# R601F.net
KiCad netlist of a schematic drawn in EAGLE
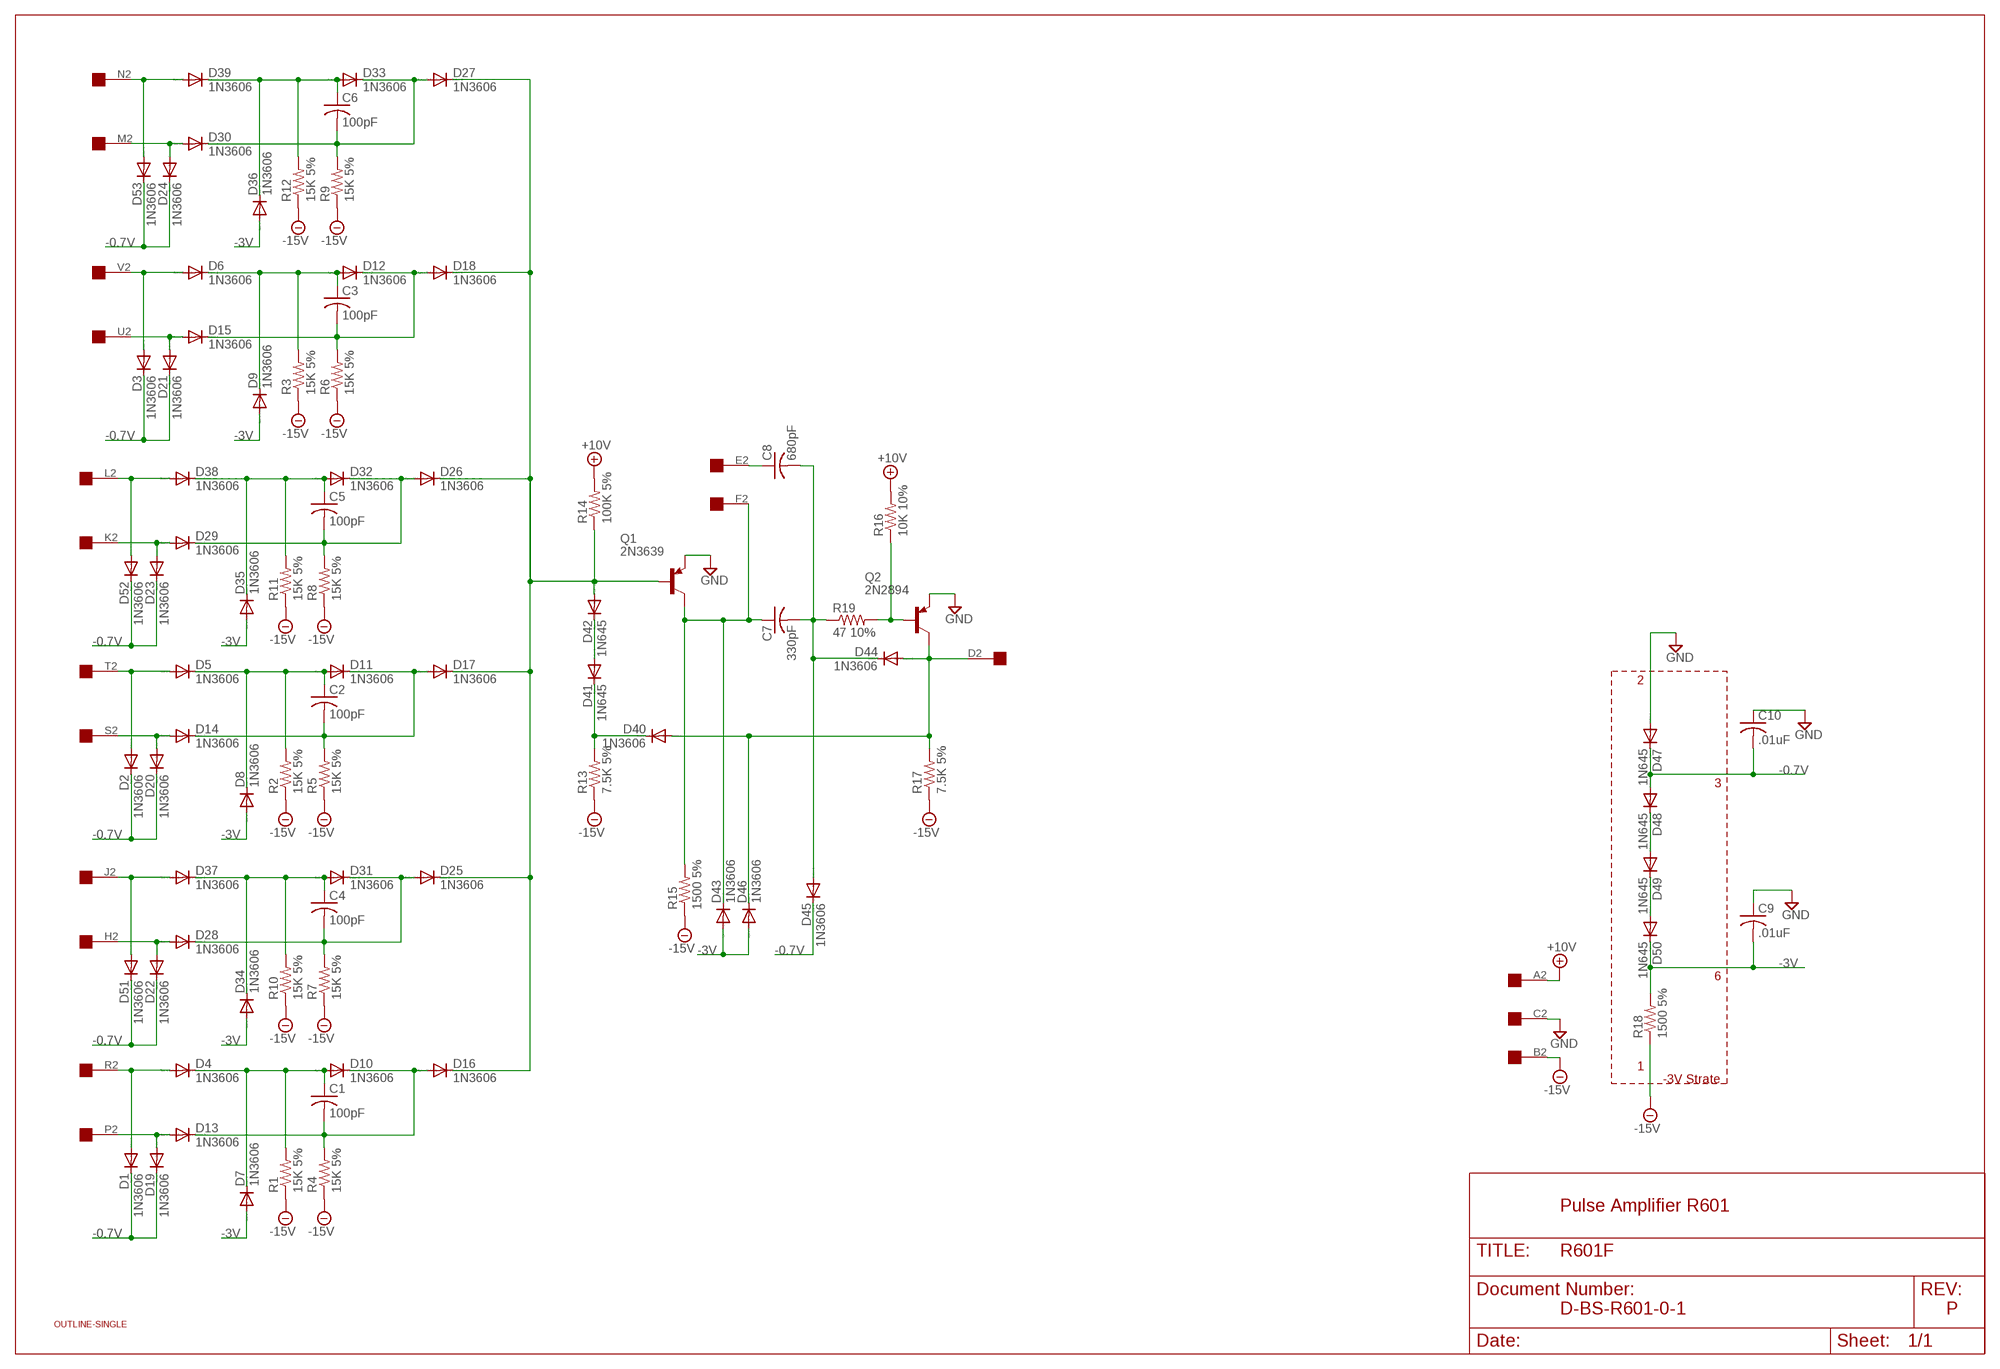
[diagram p0: schematic, sheet 1]

(export (version "E")
  (design (tool "Eeschema 10.0.6"))
  (components
    (comp (ref "C1")
      (value "100pF")
      (footprint "eagle-import:C050-025X075")
      (libsource (lib "eagle-import") (part "C-US050-025X075"))
    )
    (comp (ref "C2")
      (value "100pF")
      (footprint "eagle-import:C050-025X075")
      (libsource (lib "eagle-import") (part "C-US050-025X075"))
    )
    (comp (ref "C3")
      (value "100pF")
      (footprint "eagle-import:C050-025X075")
      (libsource (lib "eagle-import") (part "C-US050-025X075"))
    )
    (comp (ref "C4")
      (value "100pF")
      (footprint "eagle-import:C050-025X075")
      (libsource (lib "eagle-import") (part "C-US050-025X075"))
    )
    (comp (ref "C5")
      (value "100pF")
      (footprint "eagle-import:C050-025X075")
      (libsource (lib "eagle-import") (part "C-US050-025X075"))
    )
    (comp (ref "C6")
      (value "100pF")
      (footprint "eagle-import:C050-025X075")
      (libsource (lib "eagle-import") (part "C-US050-025X075"))
    )
    (comp (ref "C7")
      (value "330pF")
      (footprint "eagle-import:C050-025X075")
      (libsource (lib "eagle-import") (part "C-US050-025X075"))
    )
    (comp (ref "C8")
      (value "680pF")
      (footprint "eagle-import:C050-025X075")
      (libsource (lib "eagle-import") (part "C-US050-025X075"))
    )
    (comp (ref "C9")
      (value ".01uF")
      (footprint "eagle-import:C050-025X075")
      (libsource (lib "eagle-import") (part "C-US050-025X075"))
    )
    (comp (ref "C10")
      (value ".01uF")
      (footprint "eagle-import:C050-025X075")
      (libsource (lib "eagle-import") (part "C-US050-025X075"))
    )
    (comp (ref "D1")
      (value "1N3606")
      (footprint "eagle-import:DO35-10")
      (libsource (lib "eagle-import") (part "1N4148DO35-10"))
    )
    (comp (ref "D2")
      (value "1N3606")
      (footprint "eagle-import:DO35-10")
      (libsource (lib "eagle-import") (part "1N4148DO35-10"))
    )
    (comp (ref "D3")
      (value "1N3606")
      (footprint "eagle-import:DO35-10")
      (libsource (lib "eagle-import") (part "1N4148DO35-10"))
    )
    (comp (ref "D4")
      (value "1N3606")
      (footprint "eagle-import:DO35-10")
      (libsource (lib "eagle-import") (part "1N4148DO35-10"))
    )
    (comp (ref "D5")
      (value "1N3606")
      (footprint "eagle-import:DO35-10")
      (libsource (lib "eagle-import") (part "1N4148DO35-10"))
    )
    (comp (ref "D6")
      (value "1N3606")
      (footprint "eagle-import:DO35-10")
      (libsource (lib "eagle-import") (part "1N4148DO35-10"))
    )
    (comp (ref "D7")
      (value "1N3606")
      (footprint "eagle-import:DO35-10")
      (libsource (lib "eagle-import") (part "1N4148DO35-10"))
    )
    (comp (ref "D8")
      (value "1N3606")
      (footprint "eagle-import:DO35-10")
      (libsource (lib "eagle-import") (part "1N4148DO35-10"))
    )
    (comp (ref "D9")
      (value "1N3606")
      (footprint "eagle-import:DO35-10")
      (libsource (lib "eagle-import") (part "1N4148DO35-10"))
    )
    (comp (ref "D10")
      (value "1N3606")
      (footprint "eagle-import:DO35-10")
      (libsource (lib "eagle-import") (part "1N4148DO35-10"))
    )
    (comp (ref "D11")
      (value "1N3606")
      (footprint "eagle-import:DO35-10")
      (libsource (lib "eagle-import") (part "1N4148DO35-10"))
    )
    (comp (ref "D12")
      (value "1N3606")
      (footprint "eagle-import:DO35-10")
      (libsource (lib "eagle-import") (part "1N4148DO35-10"))
    )
    (comp (ref "D13")
      (value "1N3606")
      (footprint "eagle-import:DO35-10")
      (libsource (lib "eagle-import") (part "1N4148DO35-10"))
    )
    (comp (ref "D14")
      (value "1N3606")
      (footprint "eagle-import:DO35-10")
      (libsource (lib "eagle-import") (part "1N4148DO35-10"))
    )
    (comp (ref "D15")
      (value "1N3606")
      (footprint "eagle-import:DO35-10")
      (libsource (lib "eagle-import") (part "1N4148DO35-10"))
    )
    (comp (ref "D16")
      (value "1N3606")
      (footprint "eagle-import:DO35-10")
      (libsource (lib "eagle-import") (part "1N4148DO35-10"))
    )
    (comp (ref "D17")
      (value "1N3606")
      (footprint "eagle-import:DO35-10")
      (libsource (lib "eagle-import") (part "1N4148DO35-10"))
    )
    (comp (ref "D18")
      (value "1N3606")
      (footprint "eagle-import:DO35-10")
      (libsource (lib "eagle-import") (part "1N4148DO35-10"))
    )
    (comp (ref "D19")
      (value "1N3606")
      (footprint "eagle-import:DO35-10")
      (libsource (lib "eagle-import") (part "1N4148DO35-10"))
    )
    (comp (ref "D20")
      (value "1N3606")
      (footprint "eagle-import:DO35-10")
      (libsource (lib "eagle-import") (part "1N4148DO35-10"))
    )
    (comp (ref "D21")
      (value "1N3606")
      (footprint "eagle-import:DO35-10")
      (libsource (lib "eagle-import") (part "1N4148DO35-10"))
    )
    (comp (ref "D22")
      (value "1N3606")
      (footprint "eagle-import:DO35-10")
      (libsource (lib "eagle-import") (part "1N4148DO35-10"))
    )
    (comp (ref "D23")
      (value "1N3606")
      (footprint "eagle-import:DO35-10")
      (libsource (lib "eagle-import") (part "1N4148DO35-10"))
    )
    (comp (ref "D24")
      (value "1N3606")
      (footprint "eagle-import:DO35-10")
      (libsource (lib "eagle-import") (part "1N4148DO35-10"))
    )
    (comp (ref "D25")
      (value "1N3606")
      (footprint "eagle-import:DO35-10")
      (libsource (lib "eagle-import") (part "1N4148DO35-10"))
    )
    (comp (ref "D26")
      (value "1N3606")
      (footprint "eagle-import:DO35-10")
      (libsource (lib "eagle-import") (part "1N4148DO35-10"))
    )
    (comp (ref "D27")
      (value "1N3606")
      (footprint "eagle-import:DO35-10")
      (libsource (lib "eagle-import") (part "1N4148DO35-10"))
    )
    (comp (ref "D28")
      (value "1N3606")
      (footprint "eagle-import:DO35-10")
      (libsource (lib "eagle-import") (part "1N4148DO35-10"))
    )
    (comp (ref "D29")
      (value "1N3606")
      (footprint "eagle-import:DO35-10")
      (libsource (lib "eagle-import") (part "1N4148DO35-10"))
    )
    (comp (ref "D30")
      (value "1N3606")
      (footprint "eagle-import:DO35-10")
      (libsource (lib "eagle-import") (part "1N4148DO35-10"))
    )
    (comp (ref "D31")
      (value "1N3606")
      (footprint "eagle-import:DO35-10")
      (libsource (lib "eagle-import") (part "1N4148DO35-10"))
    )
    (comp (ref "D32")
      (value "1N3606")
      (footprint "eagle-import:DO35-10")
      (libsource (lib "eagle-import") (part "1N4148DO35-10"))
    )
    (comp (ref "D33")
      (value "1N3606")
      (footprint "eagle-import:DO35-10")
      (libsource (lib "eagle-import") (part "1N4148DO35-10"))
    )
    (comp (ref "D34")
      (value "1N3606")
      (footprint "eagle-import:DO35-10")
      (libsource (lib "eagle-import") (part "1N4148DO35-10"))
    )
    (comp (ref "D35")
      (value "1N3606")
      (footprint "eagle-import:DO35-10")
      (libsource (lib "eagle-import") (part "1N4148DO35-10"))
    )
    (comp (ref "D36")
      (value "1N3606")
      (footprint "eagle-import:DO35-10")
      (libsource (lib "eagle-import") (part "1N4148DO35-10"))
    )
    (comp (ref "D37")
      (value "1N3606")
      (footprint "eagle-import:DO35-10")
      (libsource (lib "eagle-import") (part "1N4148DO35-10"))
    )
    (comp (ref "D38")
      (value "1N3606")
      (footprint "eagle-import:DO35-10")
      (libsource (lib "eagle-import") (part "1N4148DO35-10"))
    )
    (comp (ref "D39")
      (value "1N3606")
      (footprint "eagle-import:DO35-10")
      (libsource (lib "eagle-import") (part "1N4148DO35-10"))
    )
    (comp (ref "D40")
      (value "1N3606")
      (footprint "eagle-import:DO35-10")
      (libsource (lib "eagle-import") (part "1N4148DO35-10"))
    )
    (comp (ref "D41")
      (value "1N645")
      (footprint "eagle-import:DO35-10")
      (libsource (lib "eagle-import") (part "1N4148DO35-10"))
    )
    (comp (ref "D42")
      (value "1N645")
      (footprint "eagle-import:DO35-10")
      (libsource (lib "eagle-import") (part "1N4148DO35-10"))
    )
    (comp (ref "D43")
      (value "1N3606")
      (footprint "eagle-import:DO35-10")
      (libsource (lib "eagle-import") (part "1N4148DO35-10"))
    )
    (comp (ref "D44")
      (value "1N3606")
      (footprint "eagle-import:DO35-10")
      (libsource (lib "eagle-import") (part "1N4148DO35-10"))
    )
    (comp (ref "D45")
      (value "1N3606")
      (footprint "eagle-import:DO35-10")
      (libsource (lib "eagle-import") (part "1N4148DO35-10"))
    )
    (comp (ref "D46")
      (value "1N3606")
      (footprint "eagle-import:DO35-10")
      (libsource (lib "eagle-import") (part "1N4148DO35-10"))
    )
    (comp (ref "D47")
      (value "1N645")
      (footprint "eagle-import:DO35-10")
      (libsource (lib "eagle-import") (part "1N4148DO35-10"))
    )
    (comp (ref "D48")
      (value "1N645")
      (footprint "eagle-import:DO35-10")
      (libsource (lib "eagle-import") (part "1N4148DO35-10"))
    )
    (comp (ref "D49")
      (value "1N645")
      (footprint "eagle-import:DO35-10")
      (libsource (lib "eagle-import") (part "1N4148DO35-10"))
    )
    (comp (ref "D50")
      (value "1N645")
      (footprint "eagle-import:DO35-10")
      (libsource (lib "eagle-import") (part "1N4148DO35-10"))
    )
    (comp (ref "D51")
      (value "1N3606")
      (footprint "eagle-import:DO35-10")
      (libsource (lib "eagle-import") (part "1N4148DO35-10"))
    )
    (comp (ref "D52")
      (value "1N3606")
      (footprint "eagle-import:DO35-10")
      (libsource (lib "eagle-import") (part "1N4148DO35-10"))
    )
    (comp (ref "D53")
      (value "1N3606")
      (footprint "eagle-import:DO35-10")
      (libsource (lib "eagle-import") (part "1N4148DO35-10"))
    )
    (comp (ref "Q1")
      (value "2N3639")
      (footprint "eagle-import:TO39")
      (libsource (lib "eagle-import") (part "2N2904"))
    )
    (comp (ref "Q2")
      (value "2N2894")
      (footprint "eagle-import:TO39")
      (libsource (lib "eagle-import") (part "2N2904"))
    )
    (comp (ref "R1")
      (value "15K 5%")
      (footprint "eagle-import:0207_10")
      (libsource (lib "eagle-import") (part "R-US_0207/10"))
    )
    (comp (ref "R2")
      (value "15K 5%")
      (footprint "eagle-import:0207_10")
      (libsource (lib "eagle-import") (part "R-US_0207/10"))
    )
    (comp (ref "R3")
      (value "15K 5%")
      (footprint "eagle-import:0207_10")
      (libsource (lib "eagle-import") (part "R-US_0207/10"))
    )
    (comp (ref "R4")
      (value "15K 5%")
      (footprint "eagle-import:0207_10")
      (libsource (lib "eagle-import") (part "R-US_0207/10"))
    )
    (comp (ref "R5")
      (value "15K 5%")
      (footprint "eagle-import:0207_10")
      (libsource (lib "eagle-import") (part "R-US_0207/10"))
    )
    (comp (ref "R6")
      (value "15K 5%")
      (footprint "eagle-import:0207_10")
      (libsource (lib "eagle-import") (part "R-US_0207/10"))
    )
    (comp (ref "R7")
      (value "15K 5%")
      (footprint "eagle-import:0207_10")
      (libsource (lib "eagle-import") (part "R-US_0207/10"))
    )
    (comp (ref "R8")
      (value "15K 5%")
      (footprint "eagle-import:0207_10")
      (libsource (lib "eagle-import") (part "R-US_0207/10"))
    )
    (comp (ref "R9")
      (value "15K 5%")
      (footprint "eagle-import:0207_10")
      (libsource (lib "eagle-import") (part "R-US_0207/10"))
    )
    (comp (ref "R10")
      (value "15K 5%")
      (footprint "eagle-import:0207_10")
      (libsource (lib "eagle-import") (part "R-US_0207/10"))
    )
    (comp (ref "R11")
      (value "15K 5%")
      (footprint "eagle-import:0207_10")
      (libsource (lib "eagle-import") (part "R-US_0207/10"))
    )
    (comp (ref "R12")
      (value "15K 5%")
      (footprint "eagle-import:0207_10")
      (libsource (lib "eagle-import") (part "R-US_0207/10"))
    )
    (comp (ref "R13")
      (value "7.5K 5%")
      (footprint "eagle-import:0207_10")
      (libsource (lib "eagle-import") (part "R-US_0207/10"))
    )
    (comp (ref "R14")
      (value "100K 5%")
      (footprint "eagle-import:0207_10")
      (libsource (lib "eagle-import") (part "R-US_0207/10"))
    )
    (comp (ref "R15")
      (value "1500 5%")
      (footprint "eagle-import:0207_10")
      (libsource (lib "eagle-import") (part "R-US_0207/10"))
    )
    (comp (ref "R16")
      (value "10K 10%")
      (footprint "eagle-import:0207_10")
      (libsource (lib "eagle-import") (part "R-US_0207/10"))
    )
    (comp (ref "R17")
      (value "7.5K 5%")
      (footprint "eagle-import:0207_10")
      (libsource (lib "eagle-import") (part "R-US_0207/10"))
    )
    (comp (ref "R18")
      (value "1500 5%")
      (footprint "eagle-import:0207_10")
      (libsource (lib "eagle-import") (part "R-US_0207/10"))
    )
    (comp (ref "R19")
      (value "47 10%")
      (footprint "eagle-import:0207_10")
      (libsource (lib "eagle-import") (part "R-US_0207/10"))
    )
    (comp (ref "U$1")
      (value "OUTLINE-SINGLE")
      (footprint "eagle-import:SINGLE")
      (libsource (lib "eagle-import") (part "OUTLINE-SINGLE"))
    )
    (comp (ref "U$2")
      (value "EDGE-1")
      (footprint "eagle-import:EDGE-CON1")
      (libsource (lib "eagle-import") (part "EDGE-1"))
    )
  )
  (nets
    (net (code "1") (name "+10V") (class "Default")
      (node (ref "R14") (pin "2") (pinfunction "2_2") (pintype "passive"))
      (node (ref "R16") (pin "2") (pinfunction "2_2") (pintype "passive"))
      (node (ref "U$2") (pin "A2") (pinfunction "1_A2") (pintype "bidirectional"))
    )
    (net (code "2") (name "-15V") (class "Default")
      (node (ref "R1") (pin "1") (pinfunction "1_1") (pintype "passive"))
      (node (ref "R10") (pin "1") (pinfunction "1_1") (pintype "passive"))
      (node (ref "R11") (pin "1") (pinfunction "1_1") (pintype "passive"))
      (node (ref "R12") (pin "1") (pinfunction "1_1") (pintype "passive"))
      (node (ref "R13") (pin "1") (pinfunction "1_1") (pintype "passive"))
      (node (ref "R15") (pin "1") (pinfunction "1_1") (pintype "passive"))
      (node (ref "R17") (pin "1") (pinfunction "1_1") (pintype "passive"))
      (node (ref "R18") (pin "1") (pinfunction "1_1") (pintype "passive"))
      (node (ref "R2") (pin "1") (pinfunction "1_1") (pintype "passive"))
      (node (ref "R3") (pin "1") (pinfunction "1_1") (pintype "passive"))
      (node (ref "R4") (pin "1") (pinfunction "1_1") (pintype "passive"))
      (node (ref "R5") (pin "1") (pinfunction "1_1") (pintype "passive"))
      (node (ref "R6") (pin "1") (pinfunction "1_1") (pintype "passive"))
      (node (ref "R7") (pin "1") (pinfunction "1_1") (pintype "passive"))
      (node (ref "R8") (pin "1") (pinfunction "1_1") (pintype "passive"))
      (node (ref "R9") (pin "1") (pinfunction "1_1") (pintype "passive"))
      (node (ref "U$2") (pin "B2") (pinfunction "1_B2") (pintype "bidirectional"))
    )
    (net (code "3") (name "/-0.7V") (class "Default")
      (node (ref "C10") (pin "2") (pinfunction "2_2") (pintype "passive"))
      (node (ref "D1") (pin "C") (pinfunction "C_C") (pintype "passive"))
      (node (ref "D19") (pin "C") (pinfunction "C_C") (pintype "passive"))
      (node (ref "D2") (pin "C") (pinfunction "C_C") (pintype "passive"))
      (node (ref "D20") (pin "C") (pinfunction "C_C") (pintype "passive"))
      (node (ref "D21") (pin "C") (pinfunction "C_C") (pintype "passive"))
      (node (ref "D22") (pin "C") (pinfunction "C_C") (pintype "passive"))
      (node (ref "D23") (pin "C") (pinfunction "C_C") (pintype "passive"))
      (node (ref "D24") (pin "C") (pinfunction "C_C") (pintype "passive"))
      (node (ref "D3") (pin "C") (pinfunction "C_C") (pintype "passive"))
      (node (ref "D45") (pin "C") (pinfunction "C_C") (pintype "passive"))
      (node (ref "D47") (pin "C") (pinfunction "C_C") (pintype "passive"))
      (node (ref "D48") (pin "A") (pinfunction "A_A") (pintype "passive"))
      (node (ref "D51") (pin "C") (pinfunction "C_C") (pintype "passive"))
      (node (ref "D52") (pin "C") (pinfunction "C_C") (pintype "passive"))
      (node (ref "D53") (pin "C") (pinfunction "C_C") (pintype "passive"))
    )
    (net (code "4") (name "/-3V") (class "Default")
      (node (ref "C9") (pin "2") (pinfunction "2_2") (pintype "passive"))
      (node (ref "D34") (pin "A") (pinfunction "A_A") (pintype "passive"))
      (node (ref "D35") (pin "A") (pinfunction "A_A") (pintype "passive"))
      (node (ref "D36") (pin "A") (pinfunction "A_A") (pintype "passive"))
      (node (ref "D43") (pin "A") (pinfunction "A_A") (pintype "passive"))
      (node (ref "D46") (pin "A") (pinfunction "A_A") (pintype "passive"))
      (node (ref "D50") (pin "C") (pinfunction "C_C") (pintype "passive"))
      (node (ref "D7") (pin "A") (pinfunction "A_A") (pintype "passive"))
      (node (ref "D8") (pin "A") (pinfunction "A_A") (pintype "passive"))
      (node (ref "D9") (pin "A") (pinfunction "A_A") (pintype "passive"))
      (node (ref "R18") (pin "2") (pinfunction "2_2") (pintype "passive"))
    )
    (net (code "5") (name "GND") (class "Default")
      (node (ref "C10") (pin "1") (pinfunction "1_1") (pintype "passive"))
      (node (ref "C9") (pin "1") (pinfunction "1_1") (pintype "passive"))
      (node (ref "D47") (pin "A") (pinfunction "A_A") (pintype "passive"))
      (node (ref "Q1") (pin "1") (pinfunction "E_1") (pintype "passive"))
      (node (ref "Q2") (pin "1") (pinfunction "E_1") (pintype "passive"))
      (node (ref "U$2") (pin "C2") (pinfunction "1_C2") (pintype "bidirectional"))
    )
    (net (code "6") (name "Net-(C1-Pad1)") (class "Default")
      (node (ref "C1") (pin "1") (pinfunction "1_1") (pintype "passive"))
      (node (ref "D10") (pin "A") (pinfunction "A_A") (pintype "passive"))
      (node (ref "D4") (pin "C") (pinfunction "C_C") (pintype "passive"))
      (node (ref "D7") (pin "C") (pinfunction "C_C") (pintype "passive"))
      (node (ref "R1") (pin "2") (pinfunction "2_2") (pintype "passive"))
    )
    (net (code "7") (name "Net-(C1-Pad2)") (class "Default")
      (node (ref "C1") (pin "2") (pinfunction "2_2") (pintype "passive"))
      (node (ref "D10") (pin "C") (pinfunction "C_C") (pintype "passive"))
      (node (ref "D13") (pin "C") (pinfunction "C_C") (pintype "passive"))
      (node (ref "D16") (pin "A") (pinfunction "A_A") (pintype "passive"))
      (node (ref "R4") (pin "2") (pinfunction "2_2") (pintype "passive"))
    )
    (net (code "8") (name "Net-(C2-Pad1)") (class "Default")
      (node (ref "C2") (pin "1") (pinfunction "1_1") (pintype "passive"))
      (node (ref "D11") (pin "A") (pinfunction "A_A") (pintype "passive"))
      (node (ref "D5") (pin "C") (pinfunction "C_C") (pintype "passive"))
      (node (ref "D8") (pin "C") (pinfunction "C_C") (pintype "passive"))
      (node (ref "R2") (pin "2") (pinfunction "2_2") (pintype "passive"))
    )
    (net (code "9") (name "Net-(C2-Pad2)") (class "Default")
      (node (ref "C2") (pin "2") (pinfunction "2_2") (pintype "passive"))
      (node (ref "D11") (pin "C") (pinfunction "C_C") (pintype "passive"))
      (node (ref "D14") (pin "C") (pinfunction "C_C") (pintype "passive"))
      (node (ref "D17") (pin "A") (pinfunction "A_A") (pintype "passive"))
      (node (ref "R5") (pin "2") (pinfunction "2_2") (pintype "passive"))
    )
    (net (code "10") (name "Net-(C3-Pad1)") (class "Default")
      (node (ref "C3") (pin "1") (pinfunction "1_1") (pintype "passive"))
      (node (ref "D12") (pin "A") (pinfunction "A_A") (pintype "passive"))
      (node (ref "D6") (pin "C") (pinfunction "C_C") (pintype "passive"))
      (node (ref "D9") (pin "C") (pinfunction "C_C") (pintype "passive"))
      (node (ref "R3") (pin "2") (pinfunction "2_2") (pintype "passive"))
    )
    (net (code "11") (name "Net-(C3-Pad2)") (class "Default")
      (node (ref "C3") (pin "2") (pinfunction "2_2") (pintype "passive"))
      (node (ref "D12") (pin "C") (pinfunction "C_C") (pintype "passive"))
      (node (ref "D15") (pin "C") (pinfunction "C_C") (pintype "passive"))
      (node (ref "D18") (pin "A") (pinfunction "A_A") (pintype "passive"))
      (node (ref "R6") (pin "2") (pinfunction "2_2") (pintype "passive"))
    )
    (net (code "12") (name "Net-(C4-Pad1)") (class "Default")
      (node (ref "C4") (pin "1") (pinfunction "1_1") (pintype "passive"))
      (node (ref "D31") (pin "A") (pinfunction "A_A") (pintype "passive"))
      (node (ref "D34") (pin "C") (pinfunction "C_C") (pintype "passive"))
      (node (ref "D37") (pin "C") (pinfunction "C_C") (pintype "passive"))
      (node (ref "R10") (pin "2") (pinfunction "2_2") (pintype "passive"))
    )
    (net (code "13") (name "Net-(C4-Pad2)") (class "Default")
      (node (ref "C4") (pin "2") (pinfunction "2_2") (pintype "passive"))
      (node (ref "D25") (pin "A") (pinfunction "A_A") (pintype "passive"))
      (node (ref "D28") (pin "C") (pinfunction "C_C") (pintype "passive"))
      (node (ref "D31") (pin "C") (pinfunction "C_C") (pintype "passive"))
      (node (ref "R7") (pin "2") (pinfunction "2_2") (pintype "passive"))
    )
    (net (code "14") (name "Net-(C5-Pad1)") (class "Default")
      (node (ref "C5") (pin "1") (pinfunction "1_1") (pintype "passive"))
      (node (ref "D32") (pin "A") (pinfunction "A_A") (pintype "passive"))
      (node (ref "D35") (pin "C") (pinfunction "C_C") (pintype "passive"))
      (node (ref "D38") (pin "C") (pinfunction "C_C") (pintype "passive"))
      (node (ref "R11") (pin "2") (pinfunction "2_2") (pintype "passive"))
    )
    (net (code "15") (name "Net-(C5-Pad2)") (class "Default")
      (node (ref "C5") (pin "2") (pinfunction "2_2") (pintype "passive"))
      (node (ref "D26") (pin "A") (pinfunction "A_A") (pintype "passive"))
      (node (ref "D29") (pin "C") (pinfunction "C_C") (pintype "passive"))
      (node (ref "D32") (pin "C") (pinfunction "C_C") (pintype "passive"))
      (node (ref "R8") (pin "2") (pinfunction "2_2") (pintype "passive"))
    )
    (net (code "16") (name "Net-(C6-Pad1)") (class "Default")
      (node (ref "C6") (pin "1") (pinfunction "1_1") (pintype "passive"))
      (node (ref "D33") (pin "A") (pinfunction "A_A") (pintype "passive"))
      (node (ref "D36") (pin "C") (pinfunction "C_C") (pintype "passive"))
      (node (ref "D39") (pin "C") (pinfunction "C_C") (pintype "passive"))
      (node (ref "R12") (pin "2") (pinfunction "2_2") (pintype "passive"))
    )
    (net (code "17") (name "Net-(C6-Pad2)") (class "Default")
      (node (ref "C6") (pin "2") (pinfunction "2_2") (pintype "passive"))
      (node (ref "D27") (pin "A") (pinfunction "A_A") (pintype "passive"))
      (node (ref "D30") (pin "C") (pinfunction "C_C") (pintype "passive"))
      (node (ref "D33") (pin "C") (pinfunction "C_C") (pintype "passive"))
      (node (ref "R9") (pin "2") (pinfunction "2_2") (pintype "passive"))
    )
    (net (code "18") (name "Net-(C7-Pad2)") (class "Default")
      (node (ref "C7") (pin "2") (pinfunction "2_2") (pintype "passive"))
      (node (ref "C8") (pin "2") (pinfunction "2_2") (pintype "passive"))
      (node (ref "D44") (pin "C") (pinfunction "C_C") (pintype "passive"))
      (node (ref "D45") (pin "A") (pinfunction "A_A") (pintype "passive"))
      (node (ref "R19") (pin "1") (pinfunction "1_1") (pintype "passive"))
    )
    (net (code "19") (name "Net-(D40-PadC)") (class "Default")
      (node (ref "D40") (pin "C") (pinfunction "C_C") (pintype "passive"))
      (node (ref "D41") (pin "C") (pinfunction "C_C") (pintype "passive"))
      (node (ref "R13") (pin "2") (pinfunction "2_2") (pintype "passive"))
    )
    (net (code "20") (name "Net-(D41-PadA)") (class "Default")
      (node (ref "D41") (pin "A") (pinfunction "A_A") (pintype "passive"))
      (node (ref "D42") (pin "C") (pinfunction "C_C") (pintype "passive"))
    )
    (net (code "21") (name "Net-(D48-PadC)") (class "Default")
      (node (ref "D48") (pin "C") (pinfunction "C_C") (pintype "passive"))
      (node (ref "D49") (pin "A") (pinfunction "A_A") (pintype "passive"))
    )
    (net (code "22") (name "Net-(D49-PadC)") (class "Default")
      (node (ref "D49") (pin "C") (pinfunction "C_C") (pintype "passive"))
      (node (ref "D50") (pin "A") (pinfunction "A_A") (pintype "passive"))
    )
    (net (code "23") (name "Net-(Q1-B)") (class "Default")
      (node (ref "D16") (pin "C") (pinfunction "C_C") (pintype "passive"))
      (node (ref "D17") (pin "C") (pinfunction "C_C") (pintype "passive"))
      (node (ref "D18") (pin "C") (pinfunction "C_C") (pintype "passive"))
      (node (ref "D25") (pin "C") (pinfunction "C_C") (pintype "passive"))
      (node (ref "D26") (pin "C") (pinfunction "C_C") (pintype "passive"))
      (node (ref "D27") (pin "C") (pinfunction "C_C") (pintype "passive"))
      (node (ref "D42") (pin "A") (pinfunction "A_A") (pintype "passive"))
      (node (ref "Q1") (pin "2") (pinfunction "B_2") (pintype "passive"))
      (node (ref "R14") (pin "1") (pinfunction "1_1") (pintype "passive"))
    )
    (net (code "24") (name "Net-(Q1-C)") (class "Default")
      (node (ref "C7") (pin "1") (pinfunction "1_1") (pintype "passive"))
      (node (ref "D43") (pin "C") (pinfunction "C_C") (pintype "passive"))
      (node (ref "Q1") (pin "3") (pinfunction "C_3") (pintype "passive"))
      (node (ref "R15") (pin "2") (pinfunction "2_2") (pintype "passive"))
      (node (ref "U$2") (pin "F2") (pinfunction "1_F2") (pintype "bidirectional"))
    )
    (net (code "25") (name "Net-(Q2-B)") (class "Default")
      (node (ref "Q2") (pin "2") (pinfunction "B_2") (pintype "passive"))
      (node (ref "R16") (pin "1") (pinfunction "1_1") (pintype "passive"))
      (node (ref "R19") (pin "2") (pinfunction "2_2") (pintype "passive"))
    )
    (net (code "26") (name "Net-(Q2-C)") (class "Default")
      (node (ref "D40") (pin "A") (pinfunction "A_A") (pintype "passive"))
      (node (ref "D44") (pin "A") (pinfunction "A_A") (pintype "passive"))
      (node (ref "D46") (pin "C") (pinfunction "C_C") (pintype "passive"))
      (node (ref "Q2") (pin "3") (pinfunction "C_3") (pintype "passive"))
      (node (ref "R17") (pin "2") (pinfunction "2_2") (pintype "passive"))
      (node (ref "U$2") (pin "D2") (pinfunction "1_D2") (pintype "bidirectional"))
    )
    (net (code "27") (name "Net-(U$2E-1)") (class "Default")
      (node (ref "C8") (pin "1") (pinfunction "1_1") (pintype "passive"))
      (node (ref "U$2") (pin "E2") (pinfunction "1_E2") (pintype "bidirectional"))
    )
    (net (code "28") (name "Net-(U$2G-1)") (class "Default")
      (node (ref "D22") (pin "A") (pinfunction "A_A") (pintype "passive"))
      (node (ref "D28") (pin "A") (pinfunction "A_A") (pintype "passive"))
      (node (ref "U$2") (pin "H2") (pinfunction "1_H2") (pintype "bidirectional"))
    )
    (net (code "29") (name "Net-(U$2H-1)") (class "Default")
      (node (ref "D37") (pin "A") (pinfunction "A_A") (pintype "passive"))
      (node (ref "D51") (pin "A") (pinfunction "A_A") (pintype "passive"))
      (node (ref "U$2") (pin "J2") (pinfunction "1_J2") (pintype "bidirectional"))
    )
    (net (code "30") (name "Net-(U$2I-1)") (class "Default")
      (node (ref "D23") (pin "A") (pinfunction "A_A") (pintype "passive"))
      (node (ref "D29") (pin "A") (pinfunction "A_A") (pintype "passive"))
      (node (ref "U$2") (pin "K2") (pinfunction "1_K2") (pintype "bidirectional"))
    )
    (net (code "31") (name "Net-(U$2J-1)") (class "Default")
      (node (ref "D38") (pin "A") (pinfunction "A_A") (pintype "passive"))
      (node (ref "D52") (pin "A") (pinfunction "A_A") (pintype "passive"))
      (node (ref "U$2") (pin "L2") (pinfunction "1_L2") (pintype "bidirectional"))
    )
    (net (code "32") (name "Net-(U$2K-1)") (class "Default")
      (node (ref "D24") (pin "A") (pinfunction "A_A") (pintype "passive"))
      (node (ref "D30") (pin "A") (pinfunction "A_A") (pintype "passive"))
      (node (ref "U$2") (pin "M2") (pinfunction "1_M2") (pintype "bidirectional"))
    )
    (net (code "33") (name "Net-(U$2L-1)") (class "Default")
      (node (ref "D39") (pin "A") (pinfunction "A_A") (pintype "passive"))
      (node (ref "D53") (pin "A") (pinfunction "A_A") (pintype "passive"))
      (node (ref "U$2") (pin "N2") (pinfunction "1_N2") (pintype "bidirectional"))
    )
    (net (code "34") (name "Net-(U$2M-1)") (class "Default")
      (node (ref "D13") (pin "A") (pinfunction "A_A") (pintype "passive"))
      (node (ref "D19") (pin "A") (pinfunction "A_A") (pintype "passive"))
      (node (ref "U$2") (pin "P2") (pinfunction "1_P2") (pintype "bidirectional"))
    )
    (net (code "35") (name "Net-(U$2N-1)") (class "Default")
      (node (ref "D1") (pin "A") (pinfunction "A_A") (pintype "passive"))
      (node (ref "D4") (pin "A") (pinfunction "A_A") (pintype "passive"))
      (node (ref "U$2") (pin "R2") (pinfunction "1_R2") (pintype "bidirectional"))
    )
    (net (code "36") (name "Net-(U$2O-1)") (class "Default")
      (node (ref "D14") (pin "A") (pinfunction "A_A") (pintype "passive"))
      (node (ref "D20") (pin "A") (pinfunction "A_A") (pintype "passive"))
      (node (ref "U$2") (pin "S2") (pinfunction "1_S2") (pintype "bidirectional"))
    )
    (net (code "37") (name "Net-(U$2P-1)") (class "Default")
      (node (ref "D2") (pin "A") (pinfunction "A_A") (pintype "passive"))
      (node (ref "D5") (pin "A") (pinfunction "A_A") (pintype "passive"))
      (node (ref "U$2") (pin "T2") (pinfunction "1_T2") (pintype "bidirectional"))
    )
    (net (code "38") (name "Net-(U$2Q-1)") (class "Default")
      (node (ref "D15") (pin "A") (pinfunction "A_A") (pintype "passive"))
      (node (ref "D21") (pin "A") (pinfunction "A_A") (pintype "passive"))
      (node (ref "U$2") (pin "U2") (pinfunction "1_U2") (pintype "bidirectional"))
    )
    (net (code "39") (name "Net-(U$2R-1)") (class "Default")
      (node (ref "D3") (pin "A") (pinfunction "A_A") (pintype "passive"))
      (node (ref "D6") (pin "A") (pinfunction "A_A") (pintype "passive"))
      (node (ref "U$2") (pin "V2") (pinfunction "1_V2") (pintype "bidirectional"))
    )
  )
)
